# coin12mm_-_switched.net
KiCad netlist of a schematic drawn in EAGLE
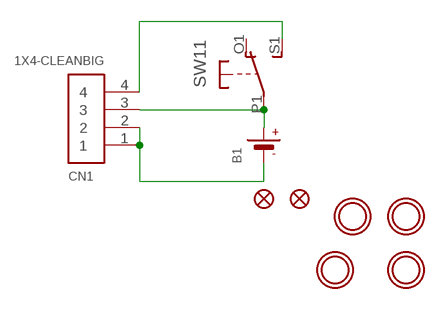
[diagram p0: schematic, sheet 1]

(export (version "E")
  (design (tool "Eeschema 10.0.6"))
  (components
    (comp (ref "B1")
      (value "BATTERYCR1220_SMT")
      (footprint "eagle-import:CR1220")
      (libsource (lib "eagle-import") (part "BATTERYCR1220_SMT"))
    )
    (comp (ref "CN1")
      (value "1X4-CLEANBIG")
      (footprint "eagle-import:1X04-CLEANBIG")
      (libsource (lib "eagle-import") (part "1X4-CLEANBIG"))
    )
    (comp (ref "FID1")
      (value "FIDUCIAL\"\"")
      (footprint "eagle-import:FIDUCIAL_1MM")
      (libsource (lib "eagle-import") (part "FIDUCIAL{dblquote}{dblquote}"))
    )
    (comp (ref "FID2")
      (value "FIDUCIAL\"\"")
      (footprint "eagle-import:FIDUCIAL_1MM")
      (libsource (lib "eagle-import") (part "FIDUCIAL{dblquote}{dblquote}"))
    )
    (comp (ref "SW1")
      (value "DPDT-EG1390")
      (footprint "eagle-import:EG1390")
      (libsource (lib "eagle-import") (part "DPDT-EG1390"))
    )
    (comp (ref "U$1")
      (value "MOUNTINGHOLE2.5")
      (footprint "eagle-import:MOUNTINGHOLE_2.5_PLATED")
      (libsource (lib "eagle-import") (part "MOUNTINGHOLE2.5"))
    )
    (comp (ref "U$2")
      (value "MOUNTINGHOLE2.5")
      (footprint "eagle-import:MOUNTINGHOLE_2.5_PLATED")
      (libsource (lib "eagle-import") (part "MOUNTINGHOLE2.5"))
    )
    (comp (ref "U$3")
      (value "MOUNTINGHOLE2.5")
      (footprint "eagle-import:MOUNTINGHOLE_2.5_PLATED")
      (libsource (lib "eagle-import") (part "MOUNTINGHOLE2.5"))
    )
    (comp (ref "U$5")
      (value "MOUNTINGHOLE2.5")
      (footprint "eagle-import:MOUNTINGHOLE_2.5_PLATED")
      (libsource (lib "eagle-import") (part "MOUNTINGHOLE2.5"))
    )
  )
  (nets
    (net (code "1") (name "Net-(B1-+)") (class "Default")
      (node (ref "B1") (pin "+$1") (pinfunction "+_+$1") (pintype "passive"))
      (node (ref "CN1") (pin "3") (pinfunction "3_3") (pintype "bidirectional"))
      (node (ref "SW1") (pin "P1") (pinfunction "P_P1") (pintype "passive"))
    )
    (net (code "2") (name "Net-(B1-Pad-)") (class "Default")
      (node (ref "B1") (pin "-") (pinfunction "-_-") (pintype "passive"))
      (node (ref "CN1") (pin "1") (pinfunction "1_1") (pintype "bidirectional"))
      (node (ref "CN1") (pin "2") (pinfunction "2_2") (pintype "bidirectional"))
    )
    (net (code "3") (name "Net-(SW1A-S)") (class "Default")
      (node (ref "CN1") (pin "4") (pinfunction "4_4") (pintype "bidirectional"))
      (node (ref "SW1") (pin "S1") (pinfunction "S_S1") (pintype "passive"))
    )
    (net (code "4") (name "unconnected-(SW1A-O-PadO1)") (class "Default")
      (node (ref "SW1") (pin "O1") (pinfunction "O_O1") (pintype "passive"))
    )
  )
)
